# sousvide.net
KiCad netlist of a schematic drawn in EAGLE
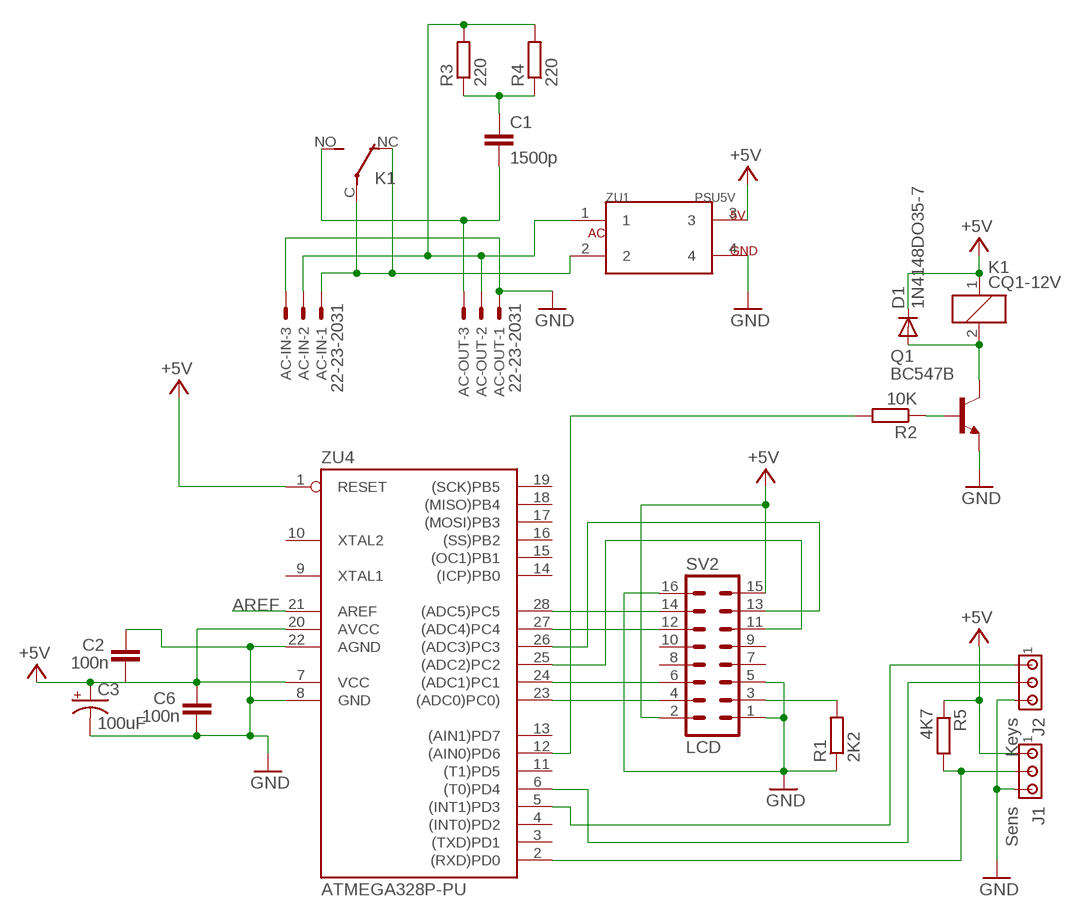
[diagram p0: schematic, sheet 1]

(export (version "E")
  (design (tool "Eeschema 10.0.6"))
  (components
    (comp (ref "AC-IN")
      (value "22-23-2031")
      (footprint "eagle-import:22-23-2031")
      (fields (field (name "MF") "MOLEX"))
      (libsource (lib "eagle-import") (part "22-23-2031"))
    )
    (comp (ref "AC-OUT")
      (value "22-23-2031")
      (footprint "eagle-import:22-23-2031")
      (fields (field (name "MF") "MOLEX"))
      (libsource (lib "eagle-import") (part "22-23-2031"))
    )
    (comp (ref "C1")
      (value "1500p")
      (footprint "eagle-import:C7.5B4")
      (libsource (lib "eagle-import") (part "C7.5/4"))
    )
    (comp (ref "C2")
      (value "100n")
      (footprint "eagle-import:C025-025X050")
      (libsource (lib "eagle-import") (part "C-EU025-025X050"))
    )
    (comp (ref "C3")
      (value "100uF")
      (footprint "eagle-import:E2,5-5")
      (libsource (lib "eagle-import") (part "CPOL-USE2.5-5"))
    )
    (comp (ref "C6")
      (value "100n")
      (footprint "eagle-import:C025-025X050")
      (libsource (lib "eagle-import") (part "C-EU025-025X050"))
    )
    (comp (ref "D1")
      (value "1N4148DO35-7")
      (footprint "eagle-import:DO35-7")
      (libsource (lib "eagle-import") (part "1N4148DO35-7"))
    )
    (comp (ref "J1")
      (value "Sens")
      (footprint "eagle-import:10X03MTA")
      (libsource (lib "eagle-import") (part "MTA03-100"))
    )
    (comp (ref "J2")
      (value "Keys")
      (footprint "eagle-import:10X03MTA")
      (libsource (lib "eagle-import") (part "MTA03-100"))
    )
    (comp (ref "K1")
      (value "CQ1-12V")
      (footprint "eagle-import:CQ1")
      (libsource (lib "eagle-import") (part "CQ1-12V"))
    )
    (comp (ref "Q1")
      (value "BC547B")
      (footprint "eagle-import:TO92")
      (libsource (lib "eagle-import") (part "BC547B"))
    )
    (comp (ref "R1")
      (value "2K2")
      (footprint "eagle-import:0204_7")
      (libsource (lib "eagle-import") (part "R-EU_0204/7"))
    )
    (comp (ref "R2")
      (value "10K")
      (footprint "eagle-import:0204_7")
      (libsource (lib "eagle-import") (part "R-EU_0204/7"))
    )
    (comp (ref "R3")
      (value "220")
      (footprint "eagle-import:0204_7")
      (libsource (lib "eagle-import") (part "R-EU_0204/7"))
    )
    (comp (ref "R4")
      (value "220")
      (footprint "eagle-import:0204_7")
      (libsource (lib "eagle-import") (part "R-EU_0204/7"))
    )
    (comp (ref "R5")
      (value "4K7")
      (footprint "eagle-import:0204_7")
      (libsource (lib "eagle-import") (part "R-EU_0204/7"))
    )
    (comp (ref "SV2")
      (value "LCD")
      (footprint "eagle-import:ML16")
      (libsource (lib "eagle-import") (part "ML16"))
    )
    (comp (ref "ZU1")
      (value "PSU5V")
      (footprint "eagle-import:USBPSU1")
      (libsource (lib "eagle-import") (part "PSU5V"))
    )
    (comp (ref "ZU4")
      (value "ATMEGA328P-PU")
      (footprint "eagle-import:DIL28-3")
      (libsource (lib "eagle-import") (part "ATMEGA328P-PU"))
    )
  )
  (nets
    (net (code "1") (name "+5V") (class "Default")
      (node (ref "C2") (pin "1") (pinfunction "1_1") (pintype "passive"))
      (node (ref "C3") (pin "+") (pinfunction "+_+") (pintype "passive"))
      (node (ref "C6") (pin "2") (pinfunction "2_2") (pintype "passive"))
      (node (ref "D1") (pin "C") (pinfunction "C_C") (pintype "passive"))
      (node (ref "J1") (pin "1") (pinfunction "1_1") (pintype "passive"))
      (node (ref "K1") (pin "1") (pinfunction "1_1") (pintype "passive"))
      (node (ref "R5") (pin "1") (pinfunction "1_1") (pintype "passive"))
      (node (ref "SV2") (pin "15") (pinfunction "15_15") (pintype "passive"))
      (node (ref "SV2") (pin "2") (pinfunction "2_2") (pintype "passive"))
      (node (ref "ZU1") (pin "3") (pinfunction "3_3") (pintype "passive"))
      (node (ref "ZU4") (pin "1") (pinfunction "RESET_1") (pintype "input"))
      (node (ref "ZU4") (pin "20") (pinfunction "AVCC_20") (pintype "power_in"))
      (node (ref "ZU4") (pin "7") (pinfunction "VCC_7") (pintype "power_in"))
    )
    (net (code "2") (name "/AREF") (class "Default")
      (node (ref "ZU4") (pin "21") (pinfunction "AREF_21") (pintype "passive"))
    )
    (net (code "3") (name "GND") (class "Default")
      (node (ref "AC-IN") (pin "3") (pinfunction "S_3") (pintype "passive"))
      (node (ref "AC-OUT") (pin "1") (pinfunction "S_1") (pintype "passive"))
      (node (ref "C2") (pin "2") (pinfunction "2_2") (pintype "passive"))
      (node (ref "C3") (pin "-") (pinfunction "-_-") (pintype "passive"))
      (node (ref "C6") (pin "1") (pinfunction "1_1") (pintype "passive"))
      (node (ref "J1") (pin "3") (pinfunction "3_3") (pintype "passive"))
      (node (ref "J2") (pin "3") (pinfunction "3_3") (pintype "passive"))
      (node (ref "Q1") (pin "1") (pinfunction "E_1") (pintype "passive"))
      (node (ref "R1") (pin "1") (pinfunction "1_1") (pintype "passive"))
      (node (ref "SV2") (pin "1") (pinfunction "1_1") (pintype "passive"))
      (node (ref "SV2") (pin "16") (pinfunction "16_16") (pintype "passive"))
      (node (ref "SV2") (pin "5") (pinfunction "5_5") (pintype "passive"))
      (node (ref "ZU1") (pin "4") (pinfunction "4_4") (pintype "passive"))
      (node (ref "ZU4") (pin "22") (pinfunction "AGND_22") (pintype "power_in"))
      (node (ref "ZU4") (pin "8") (pinfunction "GND_8") (pintype "power_in"))
    )
    (net (code "4") (name "Net-(AC-INA-S)") (class "Default")
      (node (ref "AC-IN") (pin "1") (pinfunction "S_1") (pintype "passive"))
      (node (ref "K1") (pin "C") (pinfunction "P_C") (pintype "passive"))
      (node (ref "K1") (pin "NC") (pinfunction "O_NC") (pintype "passive"))
      (node (ref "ZU1") (pin "2") (pinfunction "2_2") (pintype "passive"))
    )
    (net (code "5") (name "Net-(AC-INB-S)") (class "Default")
      (node (ref "AC-IN") (pin "2") (pinfunction "S_2") (pintype "passive"))
      (node (ref "AC-OUT") (pin "2") (pinfunction "S_2") (pintype "passive"))
      (node (ref "R3") (pin "2") (pinfunction "2_2") (pintype "passive"))
      (node (ref "R4") (pin "2") (pinfunction "2_2") (pintype "passive"))
      (node (ref "ZU1") (pin "1") (pinfunction "1_1") (pintype "passive"))
    )
    (net (code "6") (name "Net-(AC-OUTC-S)") (class "Default")
      (node (ref "AC-OUT") (pin "3") (pinfunction "S_3") (pintype "passive"))
      (node (ref "C1") (pin "2") (pinfunction "2_2") (pintype "passive"))
      (node (ref "K1") (pin "NO") (pinfunction "S_NO") (pintype "passive"))
    )
    (net (code "7") (name "Net-(C1-Pad1)") (class "Default")
      (node (ref "C1") (pin "1") (pinfunction "1_1") (pintype "passive"))
      (node (ref "R3") (pin "1") (pinfunction "1_1") (pintype "passive"))
      (node (ref "R4") (pin "1") (pinfunction "1_1") (pintype "passive"))
    )
    (net (code "8") (name "Net-(Q1-B)") (class "Default")
      (node (ref "Q1") (pin "2") (pinfunction "B_2") (pintype "passive"))
      (node (ref "R2") (pin "1") (pinfunction "1_1") (pintype "passive"))
    )
    (net (code "9") (name "Net-(Q1-C)") (class "Default")
      (node (ref "D1") (pin "A") (pinfunction "A_A") (pintype "passive"))
      (node (ref "K1") (pin "2") (pinfunction "2_2") (pintype "passive"))
      (node (ref "Q1") (pin "3") (pinfunction "C_3") (pintype "passive"))
    )
    (net (code "10") (name "Net-(R1-Pad2)") (class "Default")
      (node (ref "R1") (pin "2") (pinfunction "2_2") (pintype "passive"))
      (node (ref "SV2") (pin "3") (pinfunction "3_3") (pintype "passive"))
    )
    (net (code "11") (name "Net-(ZU4-(ADC0)PC0))") (class "Default")
      (node (ref "SV2") (pin "4") (pinfunction "4_4") (pintype "passive"))
      (node (ref "ZU4") (pin "23") (pinfunction "(ADC0)PC0)_23") (pintype "bidirectional"))
    )
    (net (code "12") (name "Net-(ZU4-(ADC1)PC1)") (class "Default")
      (node (ref "SV2") (pin "6") (pinfunction "6_6") (pintype "passive"))
      (node (ref "ZU4") (pin "24") (pinfunction "(ADC1)PC1_24") (pintype "bidirectional"))
    )
    (net (code "13") (name "Net-(ZU4-(ADC2)PC2)") (class "Default")
      (node (ref "SV2") (pin "11") (pinfunction "11_11") (pintype "passive"))
      (node (ref "ZU4") (pin "25") (pinfunction "(ADC2)PC2_25") (pintype "bidirectional"))
    )
    (net (code "14") (name "Net-(ZU4-(ADC3)PC3)") (class "Default")
      (node (ref "SV2") (pin "13") (pinfunction "13_13") (pintype "passive"))
      (node (ref "ZU4") (pin "26") (pinfunction "(ADC3)PC3_26") (pintype "bidirectional"))
    )
    (net (code "15") (name "Net-(ZU4-(ADC4)PC4)") (class "Default")
      (node (ref "SV2") (pin "12") (pinfunction "12_12") (pintype "passive"))
      (node (ref "ZU4") (pin "27") (pinfunction "(ADC4)PC4_27") (pintype "bidirectional"))
    )
    (net (code "16") (name "Net-(ZU4-(ADC5)PC5)") (class "Default")
      (node (ref "SV2") (pin "14") (pinfunction "14_14") (pintype "passive"))
      (node (ref "ZU4") (pin "28") (pinfunction "(ADC5)PC5_28") (pintype "bidirectional"))
    )
    (net (code "17") (name "Net-(ZU4-(AIN0)PD6)") (class "Default")
      (node (ref "R2") (pin "2") (pinfunction "2_2") (pintype "passive"))
      (node (ref "ZU4") (pin "12") (pinfunction "(AIN0)PD6_12") (pintype "bidirectional"))
    )
    (net (code "18") (name "Net-(ZU4-(INT1)PD3)") (class "Default")
      (node (ref "J2") (pin "1") (pinfunction "1_1") (pintype "passive"))
      (node (ref "ZU4") (pin "5") (pinfunction "(INT1)PD3_5") (pintype "bidirectional"))
    )
    (net (code "19") (name "Net-(ZU4-(RXD)PD0)") (class "Default")
      (node (ref "J1") (pin "2") (pinfunction "2_2") (pintype "passive"))
      (node (ref "R5") (pin "2") (pinfunction "2_2") (pintype "passive"))
      (node (ref "ZU4") (pin "2") (pinfunction "(RXD)PD0_2") (pintype "bidirectional"))
    )
    (net (code "20") (name "Net-(ZU4-(T0)PD4)") (class "Default")
      (node (ref "J2") (pin "2") (pinfunction "2_2") (pintype "passive"))
      (node (ref "ZU4") (pin "6") (pinfunction "(T0)PD4_6") (pintype "bidirectional"))
    )
    (net (code "21") (name "unconnected-(SV2-Pad7)") (class "Default")
      (node (ref "SV2") (pin "7") (pinfunction "7_7") (pintype "passive"))
    )
    (net (code "22") (name "unconnected-(SV2-Pad8)") (class "Default")
      (node (ref "SV2") (pin "8") (pinfunction "8_8") (pintype "passive"))
    )
    (net (code "23") (name "unconnected-(SV2-Pad9)") (class "Default")
      (node (ref "SV2") (pin "9") (pinfunction "9_9") (pintype "passive"))
    )
    (net (code "24") (name "unconnected-(SV2-Pad10)") (class "Default")
      (node (ref "SV2") (pin "10") (pinfunction "10_10") (pintype "passive"))
    )
    (net (code "25") (name "unconnected-(ZU4-(AIN1)PD7-Pad13)") (class "Default")
      (node (ref "ZU4") (pin "13") (pinfunction "(AIN1)PD7_13") (pintype "bidirectional"))
    )
    (net (code "26") (name "unconnected-(ZU4-(ICP)PB0-Pad14)") (class "Default")
      (node (ref "ZU4") (pin "14") (pinfunction "(ICP)PB0_14") (pintype "bidirectional"))
    )
    (net (code "27") (name "unconnected-(ZU4-(INT0)PD2-Pad4)") (class "Default")
      (node (ref "ZU4") (pin "4") (pinfunction "(INT0)PD2_4") (pintype "bidirectional"))
    )
    (net (code "28") (name "unconnected-(ZU4-(MISO)PB4-Pad18)") (class "Default")
      (node (ref "ZU4") (pin "18") (pinfunction "(MISO)PB4_18") (pintype "bidirectional"))
    )
    (net (code "29") (name "unconnected-(ZU4-(MOSI)PB3-Pad17)") (class "Default")
      (node (ref "ZU4") (pin "17") (pinfunction "(MOSI)PB3_17") (pintype "bidirectional"))
    )
    (net (code "30") (name "unconnected-(ZU4-(OC1)PB1-Pad15)") (class "Default")
      (node (ref "ZU4") (pin "15") (pinfunction "(OC1)PB1_15") (pintype "bidirectional"))
    )
    (net (code "31") (name "unconnected-(ZU4-(SCK)PB5-Pad19)") (class "Default")
      (node (ref "ZU4") (pin "19") (pinfunction "(SCK)PB5_19") (pintype "bidirectional"))
    )
    (net (code "32") (name "unconnected-(ZU4-(SS)PB2-Pad16)") (class "Default")
      (node (ref "ZU4") (pin "16") (pinfunction "(SS)PB2_16") (pintype "bidirectional"))
    )
    (net (code "33") (name "unconnected-(ZU4-(T1)PD5-Pad11)") (class "Default")
      (node (ref "ZU4") (pin "11") (pinfunction "(T1)PD5_11") (pintype "bidirectional"))
    )
    (net (code "34") (name "unconnected-(ZU4-(TXD)PD1-Pad3)") (class "Default")
      (node (ref "ZU4") (pin "3") (pinfunction "(TXD)PD1_3") (pintype "bidirectional"))
    )
    (net (code "35") (name "unconnected-(ZU4-XTAL1-Pad9)") (class "Default")
      (node (ref "ZU4") (pin "9") (pinfunction "XTAL1_9") (pintype "bidirectional"))
    )
    (net (code "36") (name "unconnected-(ZU4-XTAL2-Pad10)") (class "Default")
      (node (ref "ZU4") (pin "10") (pinfunction "XTAL2_10") (pintype "bidirectional"))
    )
  )
)
